# Proiect_TSC.net
KiCad netlist of a schematic drawn in EAGLE
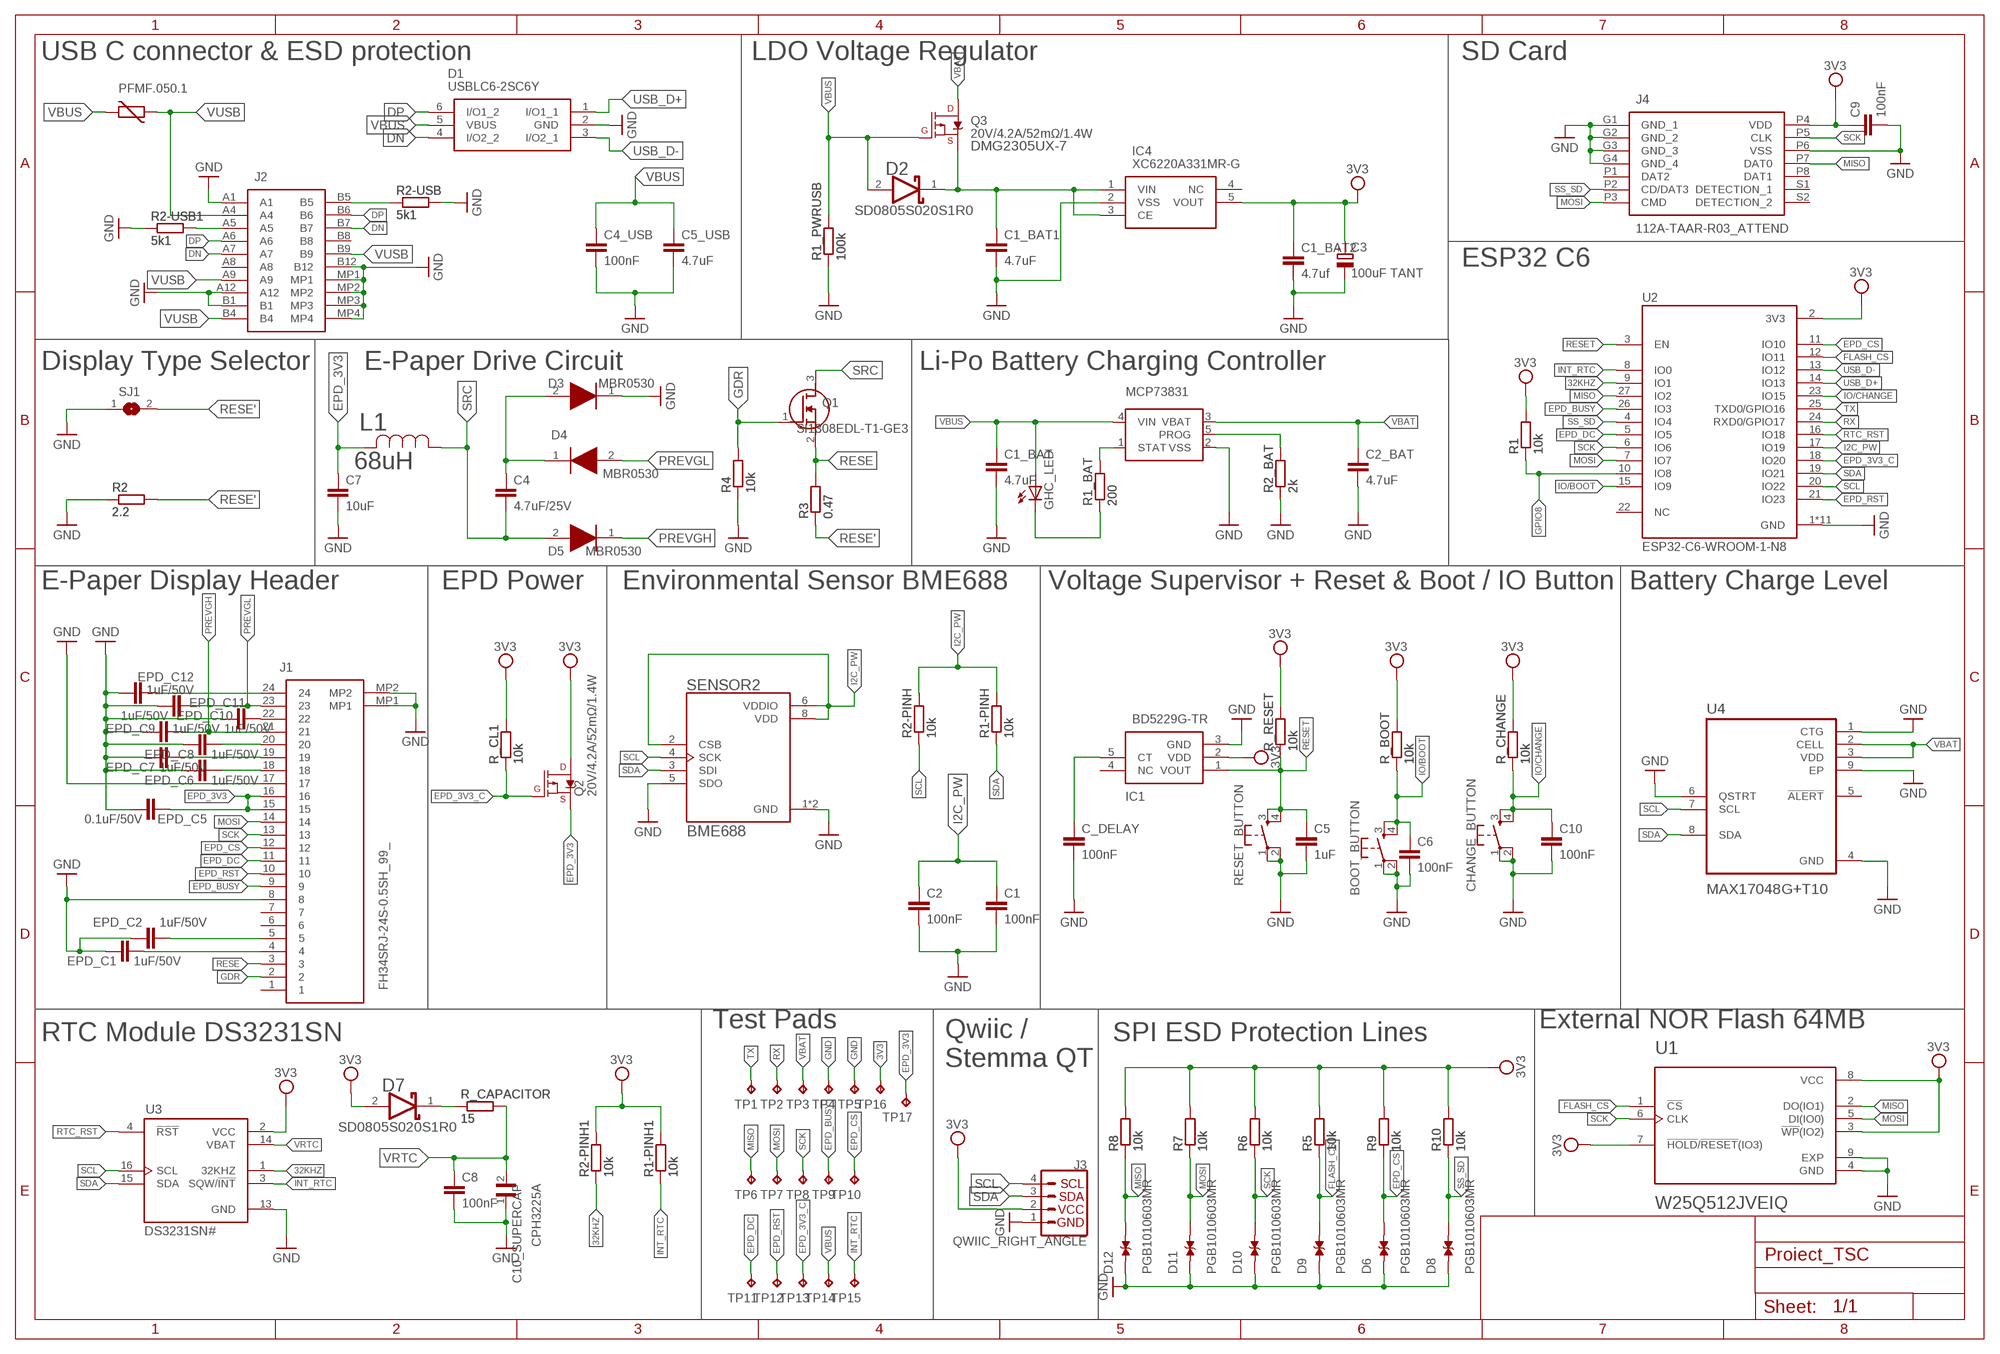
[diagram p0: schematic, sheet 1]

(export (version "E")
  (design (tool "Eeschema 10.0.6"))
  (components
    (comp (ref "BOOT_BUTTON")
      (value "BUTTON_CUSYOMV1")
      (footprint "eagle-import:MYBUTTON")
      (libsource (lib "eagle-import") (part "BUTTON_CUSYOMV1"))
    )
    (comp (ref "C1")
      (value "100nF")
      (footprint "eagle-import:ESP32_WROVER_EAGLE-LTSPICE_C0402")
      (libsource (lib "eagle-import") (part "ESP32_WROVER_EAGLE-LTSPICE_CC0402"))
    )
    (comp (ref "C1_BAT")
      (value "4.7uF")
      (footprint "eagle-import:EAGLE-LTSPICE_C0402")
      (libsource (lib "eagle-import") (part "EAGLE-LTSPICE_CC0402"))
    )
    (comp (ref "C1_BAT1")
      (value "4.7uF")
      (footprint "eagle-import:EAGLE-LTSPICE_C0402")
      (libsource (lib "eagle-import") (part "EAGLE-LTSPICE_CC0402"))
    )
    (comp (ref "C1_BAT2")
      (value "4.7uf")
      (footprint "eagle-import:EAGLE-LTSPICE_C0402")
      (libsource (lib "eagle-import") (part "EAGLE-LTSPICE_CC0402"))
    )
    (comp (ref "C2")
      (value "100nF")
      (footprint "eagle-import:ESP32_WROVER_EAGLE-LTSPICE_C0402")
      (libsource (lib "eagle-import") (part "ESP32_WROVER_EAGLE-LTSPICE_CC0402"))
    )
    (comp (ref "C2_BAT")
      (value "4.7uF")
      (footprint "eagle-import:EAGLE-LTSPICE_C0402")
      (libsource (lib "eagle-import") (part "EAGLE-LTSPICE_CC0402"))
    )
    (comp (ref "C3")
      (value "100uF TANT")
      (footprint "eagle-import:RCL_CT3528")
      (libsource (lib "eagle-import") (part "RCL_CPOL-EUCT3528"))
    )
    (comp (ref "C4")
      (value "4.7uF/25V")
      (footprint "eagle-import:ESP32_WROVER_EAGLE-LTSPICE_C0402")
      (libsource (lib "eagle-import") (part "ESP32_WROVER_EAGLE-LTSPICE_CC0402"))
    )
    (comp (ref "C4_USB")
      (value "100nF")
      (footprint "eagle-import:ESP32_WROVER_EAGLE-LTSPICE_C0402")
      (libsource (lib "eagle-import") (part "ESP32_WROVER_EAGLE-LTSPICE_CC0402"))
    )
    (comp (ref "C5")
      (value "1uF")
      (footprint "eagle-import:ESP32_WROVER_EAGLE-LTSPICE_C0402")
      (libsource (lib "eagle-import") (part "ESP32_WROVER_EAGLE-LTSPICE_CC0402"))
    )
    (comp (ref "C5_USB")
      (value "4.7uF")
      (footprint "eagle-import:ESP32_WROVER_EAGLE-LTSPICE_C0402")
      (libsource (lib "eagle-import") (part "ESP32_WROVER_EAGLE-LTSPICE_CC0402"))
    )
    (comp (ref "C6")
      (value "100nF")
      (footprint "eagle-import:ESP32_WROVER_EAGLE-LTSPICE_C0402")
      (libsource (lib "eagle-import") (part "ESP32_WROVER_EAGLE-LTSPICE_CC0402"))
    )
    (comp (ref "C7")
      (value "10uF")
      (footprint "eagle-import:ESP32_WROVER_EAGLE-LTSPICE_C0402")
      (libsource (lib "eagle-import") (part "ESP32_WROVER_EAGLE-LTSPICE_CC0402"))
    )
    (comp (ref "C8")
      (value "100nF")
      (footprint "eagle-import:ESP32_WROVER_EAGLE-LTSPICE_C0402")
      (libsource (lib "eagle-import") (part "ESP32_WROVER_EAGLE-LTSPICE_CC0402"))
    )
    (comp (ref "C9")
      (value "100nF")
      (footprint "eagle-import:ESP32_WROVER_EAGLE-LTSPICE_C0402")
      (libsource (lib "eagle-import") (part "ESP32_WROVER_EAGLE-LTSPICE_CC0402"))
    )
    (comp (ref "C10")
      (value "100nF")
      (footprint "eagle-import:ESP32_WROVER_EAGLE-LTSPICE_C0402")
      (libsource (lib "eagle-import") (part "ESP32_WROVER_EAGLE-LTSPICE_CC0402"))
    )
    (comp (ref "C10_SUPERCAP")
      (value "CPH3225A")
      (footprint "eagle-import:CAPCP3225X100N")
      (fields (field (name "MF") "Seiko Instruments"))
      (libsource (lib "eagle-import") (part "CPH3225A"))
    )
    (comp (ref "CHANGE_BUTTON")
      (value "BUTTON_CUSYOMV1")
      (footprint "eagle-import:MYBUTTON")
      (libsource (lib "eagle-import") (part "BUTTON_CUSYOMV1"))
    )
    (comp (ref "C_DELAY")
      (value "100nF")
      (footprint "eagle-import:ESP32_WROVER_EAGLE-LTSPICE_C0402")
      (libsource (lib "eagle-import") (part "ESP32_WROVER_EAGLE-LTSPICE_CC0402"))
    )
    (comp (ref "D1")
      (value "USBLC6-2SC6Y")
      (footprint "eagle-import:SOT95P280X145-6N")
      (fields (field (name "MF") "STMicroelectronics"))
      (libsource (lib "eagle-import") (part "USBLC6-2SC6Y"))
    )
    (comp (ref "D2")
      (value "SD0805S020S1R0")
      (footprint "eagle-import:ESP32_WROVER_AVX---SD0805S020S1R0_AVX_SD0805S020S1R0_0")
      (fields
        (field (name "DIGIKEY_PART_NUMBER") "478-7800-1-ND")
        (field (name "MF") "AVX")
        (field (name "MOUSER_PART_NUMBER") "581-SD0805S020S1R0")
      )
      (libsource (lib "eagle-import") (part "ESP32_WROVER_AVX---SD0805S020S1R0_AVX_SD0805S020S1R0_0_0AVX_SD0805S020S1R0_0_0"))
    )
    (comp (ref "D3")
      (value "MBR0530")
      (footprint "eagle-import:SOD3716X135N")
      (fields (field (name "MF") "ON Semiconductor"))
      (libsource (lib "eagle-import") (part "MBR0530"))
    )
    (comp (ref "D4")
      (value "MBR0530")
      (footprint "eagle-import:SOD3716X135N")
      (fields (field (name "MF") "ON Semiconductor"))
      (libsource (lib "eagle-import") (part "MBR0530"))
    )
    (comp (ref "D5")
      (value "MBR0530")
      (footprint "eagle-import:SOD3716X135N")
      (fields (field (name "MF") "ON Semiconductor"))
      (libsource (lib "eagle-import") (part "MBR0530"))
    )
    (comp (ref "D6")
      (value "PGB1010603MR")
      (footprint "eagle-import:DIOC1608X36N")
      (fields (field (name "MF") "Littelfuse Inc."))
      (libsource (lib "eagle-import") (part "PGB1010603MR"))
    )
    (comp (ref "D7")
      (value "ESP32_WROVER_AVX---SD0805S020S1R0_AVX_SD0805S020S1R0_0_0AVX_SD0805S020S1R0_0_0")
      (footprint "eagle-import:ESP32_WROVER_AVX---SD0805S020S1R0_AVX_SD0805S020S1R0_0")
      (fields
        (field (name "DIGIKEY_PART_NUMBER") "478-7800-1-ND")
        (field (name "MF") "AVX")
        (field (name "MOUSER_PART_NUMBER") "581-SD0805S020S1R0")
      )
      (libsource (lib "eagle-import") (part "ESP32_WROVER_AVX---SD0805S020S1R0_AVX_SD0805S020S1R0_0_0AVX_SD0805S020S1R0_0_0"))
    )
    (comp (ref "D8")
      (value "PGB1010603MR")
      (footprint "eagle-import:DIOC1608X36N")
      (fields (field (name "MF") "Littelfuse Inc."))
      (libsource (lib "eagle-import") (part "PGB1010603MR"))
    )
    (comp (ref "D9")
      (value "PGB1010603MR")
      (footprint "eagle-import:DIOC1608X36N")
      (fields (field (name "MF") "Littelfuse Inc."))
      (libsource (lib "eagle-import") (part "PGB1010603MR"))
    )
    (comp (ref "D10")
      (value "PGB1010603MR")
      (footprint "eagle-import:DIOC1608X36N")
      (fields (field (name "MF") "Littelfuse Inc."))
      (libsource (lib "eagle-import") (part "PGB1010603MR"))
    )
    (comp (ref "D11")
      (value "PGB1010603MR")
      (footprint "eagle-import:DIOC1608X36N")
      (fields (field (name "MF") "Littelfuse Inc."))
      (libsource (lib "eagle-import") (part "PGB1010603MR"))
    )
    (comp (ref "D12")
      (value "PGB1010603MR")
      (footprint "eagle-import:DIOC1608X36N")
      (fields (field (name "MF") "Littelfuse Inc."))
      (libsource (lib "eagle-import") (part "PGB1010603MR"))
    )
    (comp (ref "EPD_C1")
      (value "1uF/50V")
      (footprint "eagle-import:ESP32_WROVER_EAGLE-LTSPICE_C0402")
      (libsource (lib "eagle-import") (part "ESP32_WROVER_EAGLE-LTSPICE_CC0402"))
    )
    (comp (ref "EPD_C2")
      (value "1uF/50V")
      (footprint "eagle-import:ESP32_WROVER_EAGLE-LTSPICE_C0402")
      (libsource (lib "eagle-import") (part "ESP32_WROVER_EAGLE-LTSPICE_CC0402"))
    )
    (comp (ref "EPD_C5")
      (value "0.1uF/50V")
      (footprint "eagle-import:ESP32_WROVER_EAGLE-LTSPICE_C0402")
      (libsource (lib "eagle-import") (part "ESP32_WROVER_EAGLE-LTSPICE_CC0402"))
    )
    (comp (ref "EPD_C6")
      (value "1uF/50V")
      (footprint "eagle-import:ESP32_WROVER_EAGLE-LTSPICE_C0402")
      (libsource (lib "eagle-import") (part "ESP32_WROVER_EAGLE-LTSPICE_CC0402"))
    )
    (comp (ref "EPD_C7")
      (value "1uF/50V")
      (footprint "eagle-import:ESP32_WROVER_EAGLE-LTSPICE_C0402")
      (libsource (lib "eagle-import") (part "ESP32_WROVER_EAGLE-LTSPICE_CC0402"))
    )
    (comp (ref "EPD_C8")
      (value "1uF/50V")
      (footprint "eagle-import:ESP32_WROVER_EAGLE-LTSPICE_C0402")
      (libsource (lib "eagle-import") (part "ESP32_WROVER_EAGLE-LTSPICE_CC0402"))
    )
    (comp (ref "EPD_C9")
      (value "1uF/50V")
      (footprint "eagle-import:ESP32_WROVER_EAGLE-LTSPICE_C0402")
      (libsource (lib "eagle-import") (part "ESP32_WROVER_EAGLE-LTSPICE_CC0402"))
    )
    (comp (ref "EPD_C10")
      (value "1uF/50V")
      (footprint "eagle-import:ESP32_WROVER_EAGLE-LTSPICE_C0402")
      (libsource (lib "eagle-import") (part "ESP32_WROVER_EAGLE-LTSPICE_CC0402"))
    )
    (comp (ref "EPD_C11")
      (value "1uF/50V")
      (footprint "eagle-import:ESP32_WROVER_EAGLE-LTSPICE_C0402")
      (libsource (lib "eagle-import") (part "ESP32_WROVER_EAGLE-LTSPICE_CC0402"))
    )
    (comp (ref "EPD_C12")
      (value "1uF/50V")
      (footprint "eagle-import:ESP32_WROVER_EAGLE-LTSPICE_C0402")
      (libsource (lib "eagle-import") (part "ESP32_WROVER_EAGLE-LTSPICE_CC0402"))
    )
    (comp (ref "GHC_LED")
      (value "ADAFRUIT_LEDCHIP-LED0603")
      (footprint "eagle-import:ADAFRUIT_CHIP-LED0603")
      (libsource (lib "eagle-import") (part "ADAFRUIT_LEDCHIP-LED0603"))
    )
    (comp (ref "IC1")
      (value "BD5229G-TR")
      (footprint "eagle-import:SOT95P280X125-5N")
      (fields (field (name "MOUSER_PART_NUMBER") "755-BD5229G-TR"))
      (libsource (lib "eagle-import") (part "BD5229G-TR"))
    )
    (comp (ref "IC4")
      (value "XC6220A331MR-G")
      (footprint "eagle-import:SOT95P280X120-5N")
      (fields (field (name "MOUSER_PART_NUMBER") "865-XC6220A331MR-G"))
      (libsource (lib "eagle-import") (part "XC6220A331MR-G"))
    )
    (comp (ref "J1")
      (value "FH34SRJ-24S-0.5SH_99_")
      (footprint "eagle-import:FH34SRJ24S05SH99")
      (fields
        (field (name "MANUFACTURER_PART_NUMBER") "FH34SRJ-24S-0.5SH(99)")
        (field (name "MOUSER_PART_NUMBER") "798-FH34SRJ24S05SH99")
      )
      (libsource (lib "eagle-import") (part "FH34SRJ-24S-0.5SH_99_"))
    )
    (comp (ref "J2")
      (value "SAMACSYS_PARTS_USB4110-GF-A")
      (footprint "eagle-import:SAMACSYS_PARTS_USB4110GFA")
      (fields
        (field (name "MANUFACTURER_PART_NUMBER") "USB4110-GF-A")
        (field (name "MOUSER_PART_NUMBER") "640-USB4110-GF-A")
      )
      (libsource (lib "eagle-import") (part "SAMACSYS_PARTS_USB4110-GF-A"))
    )
    (comp (ref "J3")
      (value "QWIIC_RIGHT_ANGLE")
      (footprint "eagle-import:JST04_1MM_RA")
      (libsource (lib "eagle-import") (part "QWIIC_CONNECTORJS-1MM"))
    )
    (comp (ref "J4")
      (value "112A-TAAR-R03_ATTEND")
      (footprint "eagle-import:112ATAARR03ATTEND")
      (fields (field (name "MANUFACTURER_PART_NUMBER") "112A-TAAR-R03 ATTEND"))
      (libsource (lib "eagle-import") (part "112A-TAAR-R03_ATTEND"))
    )
    (comp (ref "L1")
      (value "68uH")
      (footprint "eagle-import:IND_4828-WE-TPC_WRE")
      (fields
        (field (name "MANUFACTURER_PART_NUMBER") "744043680")
        (field (name "COPYRIGHT") "Copyright (C) 2024 Ultra Librarian. All rights reserved.")
      )
      (libsource (lib "eagle-import") (part "744043680IND_4828-WE-TPC_WRE"))
    )
    (comp (ref "PFMF.050.1")
      (value "ESP32C6_VARISTORCN1812")
      (footprint "eagle-import:ESP32C6_VARISTOR_CT_CN1812")
      (libsource (lib "eagle-import") (part "ESP32C6_VARISTORCN1812"))
    )
    (comp (ref "Q1")
      (value "SI1308EDL-T1-GE3")
      (footprint "eagle-import:SOT65P210X110-3N")
      (fields (field (name "MF") "Vishay Siliconix"))
      (libsource (lib "eagle-import") (part "SI1308EDL-T1-GE3"))
    )
    (comp (ref "Q2")
      (value "20V/4.2A/52mΩ/1.4W")
      (footprint "eagle-import:ESP32_WROVER_SPARKFUN-DISCRETESEMI_SOT23-3")
      (libsource (lib "eagle-import") (part "ESP32_WROVER_SPARKFUN-DISCRETESEMI_MOSFET_PCH-DMG2305UX-7"))
    )
    (comp (ref "Q3")
      (value "20V/4.2A/52mΩ/1.4W")
      (footprint "eagle-import:ESP32_WROVER_SPARKFUN-DISCRETESEMI_SOT23-3")
      (libsource (lib "eagle-import") (part "ESP32_WROVER_SPARKFUN-DISCRETESEMI_MOSFET_PCH-DMG2305UX-7"))
    )
    (comp (ref "R1")
      (value "10k")
      (footprint "eagle-import:ESP32_WROVER_EAGLE-LTSPICE_R0402")
      (libsource (lib "eagle-import") (part "ESP32_WROVER_EAGLE-LTSPICE_RR0402"))
    )
    (comp (ref "R1-PINH")
      (value "10k")
      (footprint "eagle-import:ESP32_WROVER_EAGLE-LTSPICE_R0402")
      (libsource (lib "eagle-import") (part "ESP32_WROVER_EAGLE-LTSPICE_RR0402"))
    )
    (comp (ref "R1-PINH1")
      (value "10k")
      (footprint "eagle-import:ESP32_WROVER_EAGLE-LTSPICE_R0402")
      (libsource (lib "eagle-import") (part "ESP32_WROVER_EAGLE-LTSPICE_RR0402"))
    )
    (comp (ref "R1_BAT")
      (value "200")
      (footprint "eagle-import:ESP32_WROVER_EAGLE-LTSPICE_R0402")
      (libsource (lib "eagle-import") (part "ESP32_WROVER_EAGLE-LTSPICE_RR0402"))
    )
    (comp (ref "R1_PWRUSB")
      (value "100k")
      (footprint "eagle-import:ESP32_WROVER_EAGLE-LTSPICE_R0402")
      (libsource (lib "eagle-import") (part "ESP32_WROVER_EAGLE-LTSPICE_RR0402"))
    )
    (comp (ref "R2")
      (value "2.2")
      (footprint "eagle-import:ESP32_WROVER_EAGLE-LTSPICE_R0402")
      (libsource (lib "eagle-import") (part "ESP32_WROVER_EAGLE-LTSPICE_RR0402"))
    )
    (comp (ref "R2-PINH")
      (value "10k")
      (footprint "eagle-import:ESP32_WROVER_EAGLE-LTSPICE_R0402")
      (libsource (lib "eagle-import") (part "ESP32_WROVER_EAGLE-LTSPICE_RR0402"))
    )
    (comp (ref "R2-PINH1")
      (value "10k")
      (footprint "eagle-import:ESP32_WROVER_EAGLE-LTSPICE_R0402")
      (libsource (lib "eagle-import") (part "ESP32_WROVER_EAGLE-LTSPICE_RR0402"))
    )
    (comp (ref "R2-USB")
      (value "5k1")
      (footprint "eagle-import:ESP32_WROVER_EAGLE-LTSPICE_R0402")
      (libsource (lib "eagle-import") (part "ESP32_WROVER_EAGLE-LTSPICE_RR0402"))
    )
    (comp (ref "R2-USB1")
      (value "5k1")
      (footprint "eagle-import:ESP32_WROVER_EAGLE-LTSPICE_R0402")
      (libsource (lib "eagle-import") (part "ESP32_WROVER_EAGLE-LTSPICE_RR0402"))
    )
    (comp (ref "R2_BAT")
      (value "2k")
      (footprint "eagle-import:ESP32_WROVER_EAGLE-LTSPICE_R0402")
      (libsource (lib "eagle-import") (part "ESP32_WROVER_EAGLE-LTSPICE_RR0402"))
    )
    (comp (ref "R3")
      (value "0.47")
      (footprint "eagle-import:ESP32_WROVER_EAGLE-LTSPICE_R0402")
      (libsource (lib "eagle-import") (part "ESP32_WROVER_EAGLE-LTSPICE_RR0402"))
    )
    (comp (ref "R4")
      (value "10k")
      (footprint "eagle-import:ESP32_WROVER_EAGLE-LTSPICE_R0402")
      (libsource (lib "eagle-import") (part "ESP32_WROVER_EAGLE-LTSPICE_RR0402"))
    )
    (comp (ref "R5")
      (value "10k")
      (footprint "eagle-import:ESP32_WROVER_EAGLE-LTSPICE_R0402")
      (libsource (lib "eagle-import") (part "ESP32_WROVER_EAGLE-LTSPICE_RR0402"))
    )
    (comp (ref "R6")
      (value "10k")
      (footprint "eagle-import:ESP32_WROVER_EAGLE-LTSPICE_R0402")
      (libsource (lib "eagle-import") (part "ESP32_WROVER_EAGLE-LTSPICE_RR0402"))
    )
    (comp (ref "R7")
      (value "10k")
      (footprint "eagle-import:ESP32_WROVER_EAGLE-LTSPICE_R0402")
      (libsource (lib "eagle-import") (part "ESP32_WROVER_EAGLE-LTSPICE_RR0402"))
    )
    (comp (ref "R8")
      (value "10k")
      (footprint "eagle-import:ESP32_WROVER_EAGLE-LTSPICE_R0402")
      (libsource (lib "eagle-import") (part "ESP32_WROVER_EAGLE-LTSPICE_RR0402"))
    )
    (comp (ref "R9")
      (value "10k")
      (footprint "eagle-import:ESP32_WROVER_EAGLE-LTSPICE_R0402")
      (libsource (lib "eagle-import") (part "ESP32_WROVER_EAGLE-LTSPICE_RR0402"))
    )
    (comp (ref "R10")
      (value "10k")
      (footprint "eagle-import:ESP32_WROVER_EAGLE-LTSPICE_R0402")
      (libsource (lib "eagle-import") (part "ESP32_WROVER_EAGLE-LTSPICE_RR0402"))
    )
    (comp (ref "RESET_BUTTON")
      (value "BUTTON_CUSYOMV1")
      (footprint "eagle-import:MYBUTTON")
      (libsource (lib "eagle-import") (part "BUTTON_CUSYOMV1"))
    )
    (comp (ref "R_BOOT")
      (value "10k")
      (footprint "eagle-import:ESP32_WROVER_EAGLE-LTSPICE_R0402")
      (libsource (lib "eagle-import") (part "ESP32_WROVER_EAGLE-LTSPICE_RR0402"))
    )
    (comp (ref "R_CAPACITOR")
      (value "15")
      (footprint "eagle-import:ESP32_WROVER_EAGLE-LTSPICE_R0402")
      (libsource (lib "eagle-import") (part "ESP32_WROVER_EAGLE-LTSPICE_RR0402"))
    )
    (comp (ref "R_CHANGE")
      (value "10k")
      (footprint "eagle-import:ESP32_WROVER_EAGLE-LTSPICE_R0402")
      (libsource (lib "eagle-import") (part "ESP32_WROVER_EAGLE-LTSPICE_RR0402"))
    )
    (comp (ref "R_CL1")
      (value "10k")
      (footprint "eagle-import:ESP32_WROVER_EAGLE-LTSPICE_R0402")
      (libsource (lib "eagle-import") (part "ESP32_WROVER_EAGLE-LTSPICE_RR0402"))
    )
    (comp (ref "R_RESET")
      (value "10k")
      (footprint "eagle-import:ESP32_WROVER_EAGLE-LTSPICE_R0402")
      (libsource (lib "eagle-import") (part "ESP32_WROVER_EAGLE-LTSPICE_RR0402"))
    )
    (comp (ref "SENSOR2")
      (value "BME688")
      (footprint "eagle-import:ESP32_WROVER_BME680_PSON80P300X300X100-8N")
      (fields (field (name "MF") "Bosch Sensortec") (field (name "MP") "BME680"))
      (libsource (lib "eagle-import") (part "ESP32_WROVER_BME680_BME680"))
    )
    (comp (ref "SJ1") (value "SJ") (footprint "eagle-import:SJ") (libsource (lib "eagle-import") (part "SJ")))
    (comp (ref "TP1")
      (value "TPTP20R")
      (footprint "eagle-import:TP20R")
      (libsource (lib "eagle-import") (part "TPTP20R"))
    )
    (comp (ref "TP2")
      (value "TPTP20R")
      (footprint "eagle-import:TP20R")
      (libsource (lib "eagle-import") (part "TPTP20R"))
    )
    (comp (ref "TP3")
      (value "TPTP20R")
      (footprint "eagle-import:TP20R")
      (libsource (lib "eagle-import") (part "TPTP20R"))
    )
    (comp (ref "TP4")
      (value "TPTP20R")
      (footprint "eagle-import:TP20R")
      (libsource (lib "eagle-import") (part "TPTP20R"))
    )
    (comp (ref "TP5")
      (value "TPTP20R")
      (footprint "eagle-import:TP20R")
      (libsource (lib "eagle-import") (part "TPTP20R"))
    )
    (comp (ref "TP6")
      (value "TPTP20R")
      (footprint "eagle-import:TP20R")
      (libsource (lib "eagle-import") (part "TPTP20R"))
    )
    (comp (ref "TP7")
      (value "TPTP20R")
      (footprint "eagle-import:TP20R")
      (libsource (lib "eagle-import") (part "TPTP20R"))
    )
    (comp (ref "TP8")
      (value "TPTP20R")
      (footprint "eagle-import:TP20R")
      (libsource (lib "eagle-import") (part "TPTP20R"))
    )
    (comp (ref "TP9")
      (value "TPTP20R")
      (footprint "eagle-import:TP20R")
      (libsource (lib "eagle-import") (part "TPTP20R"))
    )
    (comp (ref "TP10")
      (value "TPTP20R")
      (footprint "eagle-import:TP20R")
      (libsource (lib "eagle-import") (part "TPTP20R"))
    )
    (comp (ref "TP11")
      (value "TPTP20R")
      (footprint "eagle-import:TP20R")
      (libsource (lib "eagle-import") (part "TPTP20R"))
    )
    (comp (ref "TP12")
      (value "TPTP20R")
      (footprint "eagle-import:TP20R")
      (libsource (lib "eagle-import") (part "TPTP20R"))
    )
    (comp (ref "TP13")
      (value "TPTP20R")
      (footprint "eagle-import:TP20R")
      (libsource (lib "eagle-import") (part "TPTP20R"))
    )
    (comp (ref "TP14")
      (value "TPTP20R")
      (footprint "eagle-import:TP20R")
      (libsource (lib "eagle-import") (part "TPTP20R"))
    )
    (comp (ref "TP15")
      (value "TPTP20R")
      (footprint "eagle-import:TP20R")
      (libsource (lib "eagle-import") (part "TPTP20R"))
    )
    (comp (ref "TP16")
      (value "TPTP20R")
      (footprint "eagle-import:TP20R")
      (libsource (lib "eagle-import") (part "TPTP20R"))
    )
    (comp (ref "TP17")
      (value "TPTP20R")
      (footprint "eagle-import:TP20R")
      (libsource (lib "eagle-import") (part "TPTP20R"))
    )
    (comp (ref "U")
      (value "MCP73831")
      (footprint "eagle-import:ESP32_WROVER_SPARKFUN-IC-POWER_SOT23-5")
      (libsource (lib "eagle-import") (part "ESP32_WROVER_SPARKFUN-IC-POWER_MCP73831"))
    )
    (comp (ref "U1")
      (value "W25Q512JVEIQ")
      (footprint "eagle-import:SON127P600X800X80-9N")
      (fields (field (name "MF") "Winbond Electronics"))
      (libsource (lib "eagle-import") (part "W25Q512JVEIQ"))
    )
    (comp (ref "U2")
      (value "ESP32-C6-WROOM-1-N8")
      (footprint "eagle-import:XCVR_ESP32-C6-WROOM-1-N8")
      (fields (field (name "MF") "Espressif Systems"))
      (libsource (lib "eagle-import") (part "ESP32-C6-WROOM-1-N8"))
    )
    (comp (ref "U3")
      (value "DS3231SN#")
      (footprint "eagle-import:SOIC127P1032X265-16N")
      (fields (field (name "MF") "Analog Devices"))
      (libsource (lib "eagle-import") (part "DS3231SN#"))
    )
    (comp (ref "U4")
      (value "MAX17048G+T10")
      (footprint "eagle-import:SON50P200X200X80-9N")
      (fields (field (name "MF") "Analog Devices"))
      (libsource (lib "eagle-import") (part "MAX17048G+T10"))
    )
  )
  (nets
    (net (code "1") (name "3V3") (class "Default")
      (node (ref "C1_BAT2") (pin "1") (pinfunction "1_1") (pintype "passive"))
      (node (ref "C3") (pin "+") (pinfunction "+_+") (pintype "passive"))
      (node (ref "C9") (pin "1") (pinfunction "1_1") (pintype "passive"))
      (node (ref "D7") (pin "2") (pinfunction "ANODE_2") (pintype "bidirectional"))
      (node (ref "IC1") (pin "2") (pinfunction "VDD_2") (pintype "bidirectional"))
      (node (ref "IC4") (pin "5") (pinfunction "VOUT_5") (pintype "bidirectional"))
      (node (ref "J3") (pin "2") (pinfunction "2_2") (pintype "power_in"))
      (node (ref "J4") (pin "P4") (pinfunction "VDD_P4") (pintype "bidirectional"))
      (node (ref "Q2") (pin "3") (pinfunction "D_3") (pintype "bidirectional"))
      (node (ref "R1") (pin "2") (pinfunction "2_2") (pintype "passive"))
      (node (ref "R1-PINH1") (pin "2") (pinfunction "2_2") (pintype "passive"))
      (node (ref "R10") (pin "2") (pinfunction "2_2") (pintype "passive"))
      (node (ref "R2-PINH1") (pin "2") (pinfunction "2_2") (pintype "passive"))
      (node (ref "R5") (pin "2") (pinfunction "2_2") (pintype "passive"))
      (node (ref "R6") (pin "2") (pinfunction "2_2") (pintype "passive"))
      (node (ref "R7") (pin "2") (pinfunction "2_2") (pintype "passive"))
      (node (ref "R8") (pin "2") (pinfunction "2_2") (pintype "passive"))
      (node (ref "R9") (pin "2") (pinfunction "2_2") (pintype "passive"))
      (node (ref "R_BOOT") (pin "2") (pinfunction "2_2") (pintype "passive"))
      (node (ref "R_CHANGE") (pin "2") (pinfunction "2_2") (pintype "passive"))
      (node (ref "R_CL1") (pin "2") (pinfunction "2_2") (pintype "passive"))
      (node (ref "R_RESET") (pin "2") (pinfunction "2_2") (pintype "passive"))
      (node (ref "TP16") (pin "TP") (pinfunction "TP_TP") (pintype "input"))
      (node (ref "U1") (pin "3") (pinfunction "~{WP}(IO2)_3") (pintype "bidirectional"))
      (node (ref "U1") (pin "7") (pinfunction "~{HOLD}/~{RESET}(IO3)_7") (pintype "bidirectional"))
      (node (ref "U1") (pin "8") (pinfunction "VCC_8") (pintype "power_in"))
      (node (ref "U2") (pin "2") (pinfunction "3V3_2") (pintype "power_in"))
      (node (ref "U3") (pin "2") (pinfunction "VCC_2") (pintype "power_in"))
    )
    (net (code "2") (name "32KHZ") (class "Default")
      (node (ref "R2-PINH1") (pin "1") (pinfunction "1_1") (pintype "passive"))
      (node (ref "U2") (pin "9") (pinfunction "IO1_9") (pintype "bidirectional"))
      (node (ref "U3") (pin "1") (pinfunction "32KHZ_1") (pintype "output"))
    )
    (net (code "3") (name "DN") (class "Default")
      (node (ref "D1") (pin "4") (pinfunction "I/O2_2_4") (pintype "bidirectional"))
      (node (ref "J2") (pin "A7") (pinfunction "A7_A7") (pintype "bidirectional"))
      (node (ref "J2") (pin "B7") (pinfunction "B7_B7") (pintype "bidirectional"))
    )
    (net (code "4") (name "DP") (class "Default")
      (node (ref "D1") (pin "6") (pinfunction "I/O1_2_6") (pintype "bidirectional"))
      (node (ref "J2") (pin "A6") (pinfunction "A6_A6") (pintype "bidirectional"))
      (node (ref "J2") (pin "B6") (pinfunction "B6_B6") (pintype "bidirectional"))
    )
    (net (code "5") (name "EPD_3V3") (class "Default")
      (node (ref "C7") (pin "1") (pinfunction "1_1") (pintype "passive"))
      (node (ref "EPD_C5") (pin "2") (pinfunction "2_2") (pintype "passive"))
      (node (ref "J1") (pin "15") (pinfunction "15_15") (pintype "bidirectional"))
      (node (ref "J1") (pin "16") (pinfunction "16_16") (pintype "bidirectional"))
      (node (ref "L1") (pin "2") (pinfunction "2_2") (pintype "passive"))
      (node (ref "Q2") (pin "2") (pinfunction "S_2") (pintype "bidirectional"))
      (node (ref "TP17") (pin "TP") (pinfunction "TP_TP") (pintype "input"))
    )
    (net (code "6") (name "EPD_3V3_C") (class "Default")
      (node (ref "Q2") (pin "1") (pinfunction "G_1") (pintype "bidirectional"))
      (node (ref "R_CL1") (pin "1") (pinfunction "1_1") (pintype "passive"))
      (node (ref "TP13") (pin "TP") (pinfunction "TP_TP") (pintype "input"))
      (node (ref "U2") (pin "18") (pinfunction "IO20_18") (pintype "bidirectional"))
    )
    (net (code "7") (name "EPD_BUSY") (class "Default")
      (node (ref "J1") (pin "9") (pinfunction "9_9") (pintype "bidirectional"))
      (node (ref "TP9") (pin "TP") (pinfunction "TP_TP") (pintype "input"))
      (node (ref "U2") (pin "26") (pinfunction "IO3_26") (pintype "bidirectional"))
    )
    (net (code "8") (name "EPD_CS") (class "Default")
      (node (ref "D6") (pin "2") (pinfunction "2_2") (pintype "passive"))
      (node (ref "J1") (pin "12") (pinfunction "12_12") (pintype "bidirectional"))
      (node (ref "R9") (pin "1") (pinfunction "1_1") (pintype "passive"))
      (node (ref "TP10") (pin "TP") (pinfunction "TP_TP") (pintype "input"))
      (node (ref "U2") (pin "11") (pinfunction "IO10_11") (pintype "bidirectional"))
    )
    (net (code "9") (name "EPD_DC") (class "Default")
      (node (ref "J1") (pin "11") (pinfunction "11_11") (pintype "bidirectional"))
      (node (ref "TP11") (pin "TP") (pinfunction "TP_TP") (pintype "input"))
      (node (ref "U2") (pin "5") (pinfunction "IO5_5") (pintype "bidirectional"))
    )
    (net (code "10") (name "EPD_RST") (class "Default")
      (node (ref "J1") (pin "10") (pinfunction "10_10") (pintype "bidirectional"))
      (node (ref "TP12") (pin "TP") (pinfunction "TP_TP") (pintype "input"))
      (node (ref "U2") (pin "21") (pinfunction "IO23_21") (pintype "bidirectional"))
    )
    (net (code "11") (name "FLASH_CS") (class "Default")
      (node (ref "D9") (pin "2") (pinfunction "2_2") (pintype "passive"))
      (node (ref "R5") (pin "1") (pinfunction "1_1") (pintype "passive"))
      (node (ref "U1") (pin "1") (pinfunction "~{CS}_1") (pintype "input"))
      (node (ref "U2") (pin "12") (pinfunction "IO11_12") (pintype "bidirectional"))
    )
    (net (code "12") (name "GDR") (class "Default")
      (node (ref "J1") (pin "2") (pinfunction "2_2") (pintype "bidirectional"))
      (node (ref "Q1") (pin "1") (pinfunction "G_1") (pintype "bidirectional"))
      (node (ref "R4") (pin "2") (pinfunction "2_2") (pintype "passive"))
    )
    (net (code "13") (name "GND") (class "Default")
      (node (ref "BOOT_BUTTON") (pin "1") (pinfunction "1_1") (pintype "passive"))
      (node (ref "BOOT_BUTTON") (pin "2") (pinfunction "2_2") (pintype "passive"))
      (node (ref "C1") (pin "2") (pinfunction "2_2") (pintype "passive"))
      (node (ref "C10") (pin "2") (pinfunction "2_2") (pintype "passive"))
      (node (ref "C10_SUPERCAP") (pin "1") (pinfunction "1_1") (pintype "passive"))
      (node (ref "C1_BAT") (pin "2") (pinfunction "2_2") (pintype "passive"))
      (node (ref "C1_BAT1") (pin "2") (pinfunction "2_2") (pintype "passive"))
      (node (ref "C1_BAT2") (pin "2") (pinfunction "2_2") (pintype "passive"))
      (node (ref "C2") (pin "2") (pinfunction "2_2") (pintype "passive"))
      (node (ref "C2_BAT") (pin "2") (pinfunction "2_2") (pintype "passive"))
      (node (ref "C3") (pin "-") (pinfunction "-_-") (pintype "passive"))
      (node (ref "C4_USB") (pin "2") (pinfunction "2_2") (pintype "passive"))
      (node (ref "C5") (pin "2") (pinfunction "2_2") (pintype "passive"))
      (node (ref "C5_USB") (pin "2") (pinfunction "2_2") (pintype "passive"))
      (node (ref "C6") (pin "2") (pinfunction "2_2") (pintype "passive"))
      (node (ref "C7") (pin "2") (pinfunction "2_2") (pintype "passive"))
      (node (ref "C8") (pin "2") (pinfunction "2_2") (pintype "passive"))
      (node (ref "C9") (pin "2") (pinfunction "2_2") (pintype "passive"))
      (node (ref "CHANGE_BUTTON") (pin "1") (pinfunction "1_1") (pintype "passive"))
      (node (ref "CHANGE_BUTTON") (pin "2") (pinfunction "2_2") (pintype "passive"))
      (node (ref "C_DELAY") (pin "2") (pinfunction "2_2") (pintype "passive"))
      (node (ref "D1") (pin "2") (pinfunction "GND_2") (pintype "bidirectional"))
      (node (ref "D10") (pin "1") (pinfunction "1_1") (pintype "passive"))
      (node (ref "D11") (pin "1") (pinfunction "1_1") (pintype "passive"))
      (node (ref "D12") (pin "1") (pinfunction "1_1") (pintype "passive"))
      (node (ref "D3") (pin "1") (pinfunction "K_1") (pintype "bidirectional"))
      (node (ref "D6") (pin "1") (pinfunction "1_1") (pintype "passive"))
      (node (ref "D8") (pin "1") (pinfunction "1_1") (pintype "passive"))
      (node (ref "D9") (pin "1") (pinfunction "1_1") (pintype "passive"))
      (node (ref "EPD_C1") (pin "1") (pinfunction "1_1") (pintype "passive"))
      (node (ref "EPD_C10") (pin "1") (pinfunction "1_1") (pintype "passive"))
      (node (ref "EPD_C11") (pin "1") (pinfunction "1_1") (pintype "passive"))
      (node (ref "EPD_C12") (pin "1") (pinfunction "1_1") (pintype "passive"))
      (node (ref "EPD_C2") (pin "1") (pinfunction "1_1") (pintype "passive"))
      (node (ref "EPD_C5") (pin "1") (pinfunction "1_1") (pintype "passive"))
      (node (ref "EPD_C6") (pin "1") (pinfunction "1_1") (pintype "passive"))
      (node (ref "EPD_C7") (pin "1") (pinfunction "1_1") (pintype "passive"))
      (node (ref "EPD_C8") (pin "1") (pinfunction "1_1") (pintype "passive"))
      (node (ref "EPD_C9") (pin "1") (pinfunction "1_1") (pintype "passive"))
      (node (ref "IC1") (pin "3") (pinfunction "GND_3") (pintype "bidirectional"))
      (node (ref "IC4") (pin "2") (pinfunction "VSS_2") (pintype "bidirectional"))
      (node (ref "J1") (pin "17") (pinfunction "17_17") (pintype "bidirectional"))
      (node (ref "J1") (pin "8") (pinfunction "8_8") (pintype "bidirectional"))
      (node (ref "J1") (pin "MP1") (pinfunction "MP1_MP1") (pintype "bidirectional"))
      (node (ref "J1") (pin "MP2") (pinfunction "MP2_MP2") (pintype "bidirectional"))
      (node (ref "J2") (pin "A1") (pinfunction "A1_A1") (pintype "bidirectional"))
      (node (ref "J2") (pin "A12") (pinfunction "A12_A12") (pintype "bidirectional"))
      (node (ref "J2") (pin "B1") (pinfunction "B1_B1") (pintype "bidirectional"))
      (node (ref "J2") (pin "B12") (pinfunction "B12_B12") (pintype "bidirectional"))
      (node (ref "J2") (pin "MP1") (pinfunction "MP1_MP1") (pintype "bidirectional"))
      (node (ref "J2") (pin "MP2") (pinfunction "MP2_MP2") (pintype "bidirectional"))
      (node (ref "J2") (pin "MP3") (pinfunction "MP3_MP3") (pintype "bidirectional"))
      (node (ref "J2") (pin "MP4") (pinfunction "MP4_MP4") (pintype "bidirectional"))
      (node (ref "J3") (pin "1") (pinfunction "1_1") (pintype "power_in"))
      (node (ref "J4") (pin "G1") (pinfunction "GND_1_G1") (pintype "bidirectional"))
      (node (ref "J4") (pin "G2") (pinfunction "GND_2_G2") (pintype "bidirectional"))
      (node (ref "J4") (pin "G3") (pinfunction "GND_3_G3") (pintype "bidirectional"))
      (node (ref "J4") (pin "G4") (pinfunction "GND_4_G4") (pintype "bidirectional"))
      (node (ref "J4") (pin "P6") (pinfunction "VSS_P6") (pintype "bidirectional"))
      (node (ref "R1_PWRUSB") (pin "1") (pinfunction "1_1") (pintype "passive"))
      (node (ref "R2") (pin "1") (pinfunction "1_1") (pintype "passive"))
      (node (ref "R2-USB") (pin "2") (pinfunction "2_2") (pintype "passive"))
      (node (ref "R2-USB1") (pin "1") (pinfunction "1_1") (pintype "passive"))
      (node (ref "R2_BAT") (pin "1") (pinfunction "1_1") (pintype "passive"))
      (node (ref "R4") (pin "1") (pinfunction "1_1") (pintype "passive"))
      (node (ref "RESET_BUTTON") (pin "1") (pinfunction "1_1") (pintype "passive"))
      (node (ref "RESET_BUTTON") (pin "2") (pinfunction "2_2") (pintype "passive"))
      (node (ref "SENSOR2") (pin "1") (pinfunction "GND_1") (pintype "power_in"))
      (node (ref "SENSOR2") (pin "5") (pinfunction "SDO_5") (pintype "bidirectional"))
      (node (ref "SENSOR2") (pin "7") (pinfunction "GND_7") (pintype "power_in"))
      (node (ref "SJ1") (pin "1") (pinfunction "1_1") (pintype "passive"))
      (node (ref "TP4") (pin "TP") (pinfunction "TP_TP") (pintype "input"))
      (node (ref "TP5") (pin "TP") (pinfunction "TP_TP") (pintype "input"))
      (node (ref "U") (pin "2") (pinfunction "VSS_2") (pintype "power_in"))
      (node (ref "U1") (pin "4") (pinfunction "GND_4") (pintype "power_in"))
      (node (ref "U1") (pin "9") (pinfunction "EXP_9") (pintype "passive"))
      (node (ref "U2") (pin "1") (pinfunction "GND_1") (pintype "power_in"))
      (node (ref "U2") (pin "28") (pinfunction "GND_28") (pintype "power_in"))
      (node (ref "U2") (pin "29_1") (pinfunction "GND_29_1") (pintype "power_in"))
      (node (ref "U2") (pin "29_2") (pinfunction "GND_29_2") (pintype "power_in"))
      (node (ref "U2") (pin "29_3") (pinfunction "GND_29_3") (pintype "power_in"))
      (node (ref "U2") (pin "29_4") (pinfunction "GND_29_4") (pintype "power_in"))
      (node (ref "U2") (pin "29_5") (pinfunction "GND_29_5") (pintype "power_in"))
      (node (ref "U2") (pin "29_6") (pinfunction "GND_29_6") (pintype "power_in"))
      (node (ref "U2") (pin "29_7") (pinfunction "GND_29_7") (pintype "power_in"))
      (node (ref "U2") (pin "29_8") (pinfunction "GND_29_8") (pintype "power_in"))
      (node (ref "U2") (pin "29_9") (pinfunction "GND_29_9") (pintype "power_in"))
      (node (ref "U3") (pin "13") (pinfunction "GND_13") (pintype "power_in"))
      (node (ref "U4") (pin "1") (pinfunction "CTG_1") (pintype "power_in"))
      (node (ref "U4") (pin "4") (pinfunction "GND_4") (pintype "power_in"))
      (node (ref "U4") (pin "6") (pinfunction "QSTRT_6") (pintype "input"))
      (node (ref "U4") (pin "9") (pinfunction "EP_9") (pintype "power_in"))
    )
    (net (code "14") (name "GPIO8") (class "Default")
      (node (ref "R1") (pin "1") (pinfunction "1_1") (pintype "passive"))
      (node (ref "U2") (pin "10") (pinfunction "IO8_10") (pintype "bidirectional"))
    )
    (net (code "15") (name "I2C_PW") (class "Default")
      (node (ref "C1") (pin "1") (pinfunction "1_1") (pintype "passive"))
      (node (ref "C2") (pin "1") (pinfunction "1_1") (pintype "passive"))
      (node (ref "R1-PINH") (pin "2") (pinfunction "2_2") (pintype "passive"))
      (node (ref "R2-PINH") (pin "2") (pinfunction "2_2") (pintype "passive"))
      (node (ref "SENSOR2") (pin "2") (pinfunction "CSB_2") (pintype "input"))
      (node (ref "SENSOR2") (pin "6") (pinfunction "VDDIO_6") (pintype "power_in"))
      (node (ref "SENSOR2") (pin "8") (pinfunction "VDD_8") (pintype "power_in"))
      (node (ref "U2") (pin "17") (pinfunction "IO19_17") (pintype "bidirectional"))
    )
    (net (code "16") (name "INT_RTC") (class "Default")
      (node (ref "R1-PINH1") (pin "1") (pinfunction "1_1") (pintype "passive"))
      (node (ref "TP15") (pin "TP") (pinfunction "TP_TP") (pintype "input"))
      (node (ref "U2") (pin "8") (pinfunction "IO0_8") (pintype "bidirectional"))
      (node (ref "U3") (pin "3") (pinfunction "SQW/~{INT}_3") (pintype "output"))
    )
    (net (code "17") (name "IO{slash}BOOT") (class "Default")
      (node (ref "BOOT_BUTTON") (pin "3") (pinfunction "3_3") (pintype "passive"))
      (node (ref "BOOT_BUTTON") (pin "4") (pinfunction "4_4") (pintype "passive"))
      (node (ref "C6") (pin "1") (pinfunction "1_1") (pintype "passive"))
      (node (ref "R_BOOT") (pin "1") (pinfunction "1_1") (pintype "passive"))
      (node (ref "U2") (pin "15") (pinfunction "IO9_15") (pintype "bidirectional"))
    )
    (net (code "18") (name "IO{slash}CHANGE") (class "Default")
      (node (ref "C10") (pin "1") (pinfunction "1_1") (pintype "passive"))
      (node (ref "CHANGE_BUTTON") (pin "3") (pinfunction "3_3") (pintype "passive"))
      (node (ref "CHANGE_BUTTON") (pin "4") (pinfunction "4_4") (pintype "passive"))
      (node (ref "R_CHANGE") (pin "1") (pinfunction "1_1") (pintype "passive"))
      (node (ref "U2") (pin "23") (pinfunction "IO15_23") (pintype "bidirectional"))
    )
    (net (code "19") (name "MISO") (class "Default")
      (node (ref "D12") (pin "2") (pinfunction "2_2") (pintype "passive"))
      (node (ref "J4") (pin "P7") (pinfunction "DAT0_P7") (pintype "bidirectional"))
      (node (ref "R8") (pin "1") (pinfunction "1_1") (pintype "passive"))
      (node (ref "TP6") (pin "TP") (pinfunction "TP_TP") (pintype "input"))
      (node (ref "U1") (pin "2") (pinfunction "DO(IO1)_2") (pintype "bidirectional"))
      (node (ref "U2") (pin "27") (pinfunction "IO2_27") (pintype "bidirectional"))
    )
    (net (code "20") (name "MOSI") (class "Default")
      (node (ref "D11") (pin "2") (pinfunction "2_2") (pintype "passive"))
      (node (ref "J1") (pin "14") (pinfunction "14_14") (pintype "bidirectional"))
      (node (ref "J4") (pin "P3") (pinfunction "CMD_P3") (pintype "bidirectional"))
      (node (ref "R7") (pin "1") (pinfunction "1_1") (pintype "passive"))
      (node (ref "TP7") (pin "TP") (pinfunction "TP_TP") (pintype "input"))
      (node (ref "U1") (pin "5") (pinfunction "DI(IO0)_5") (pintype "bidirectional"))
      (node (ref "U2") (pin "7") (pinfunction "IO7_7") (pintype "bidirectional"))
    )
    (net (code "21") (name "Net-(D2-CATHODE)") (class "Default")
      (node (ref "C1_BAT1") (pin "1") (pinfunction "1_1") (pintype "passive"))
      (node (ref "D2") (pin "1") (pinfunction "CATHODE_1") (pintype "bidirectional"))
      (node (ref "IC4") (pin "1") (pinfunction "VIN_1") (pintype "bidirectional"))
      (node (ref "IC4") (pin "3") (pinfunction "CE_3") (pintype "bidirectional"))
      (node (ref "Q3") (pin "2") (pinfunction "S_2") (pintype "bidirectional"))
    )
    (net (code "22") (name "Net-(D3-A)") (class "Default")
      (node (ref "C4") (pin "1") (pinfunction "1_1") (pintype "passive"))
      (node (ref "D3") (pin "2") (pinfunction "A_2") (pintype "bidirectional"))
      (node (ref "D4") (pin "1") (pinfunction "K_1") (pintype "bidirectional"))
    )
    (net (code "23") (name "Net-(D7-CATHODE)") (class "Default")
      (node (ref "D7") (pin "1") (pinfunction "CATHODE_1") (pintype "bidirectional"))
      (node (ref "R_CAPACITOR") (pin "1") (pinfunction "1_1") (pintype "passive"))
    )
    (net (code "24") (name "Net-(EPD_C1-Pad2)") (class "Default")
      (node (ref "EPD_C1") (pin "2") (pinfunction "2_2") (pintype "passive"))
      (node (ref "J1") (pin "4") (pinfunction "4_4") (pintype "bidirectional"))
    )
    (net (code "25") (name "Net-(EPD_C2-Pad2)") (class "Default")
      (node (ref "EPD_C2") (pin "2") (pinfunction "2_2") (pintype "passive"))
      (node (ref "J1") (pin "5") (pinfunction "5_5") (pintype "bidirectional"))
    )
    (net (code "26") (name "Net-(EPD_C6-Pad2)") (class "Default")
      (node (ref "EPD_C6") (pin "2") (pinfunction "2_2") (pintype "passive"))
      (node (ref "J1") (pin "18") (pinfunction "18_18") (pintype "bidirectional"))
    )
    (net (code "27") (name "Net-(EPD_C7-Pad2)") (class "Default")
      (node (ref "EPD_C7") (pin "2") (pinfunction "2_2") (pintype "passive"))
      (node (ref "J1") (pin "19") (pinfunction "19_19") (pintype "bidirectional"))
    )
    (net (code "28") (name "Net-(EPD_C8-Pad2)") (class "Default")
      (node (ref "EPD_C8") (pin "2") (pinfunction "2_2") (pintype "passive"))
      (node (ref "J1") (pin "20") (pinfunction "20_20") (pintype "bidirectional"))
    )
    (net (code "29") (name "Net-(EPD_C10-Pad2)") (class "Default")
      (node (ref "EPD_C10") (pin "2") (pinfunction "2_2") (pintype "passive"))
      (node (ref "J1") (pin "22") (pinfunction "22_22") (pintype "bidirectional"))
    )
    (net (code "30") (name "Net-(EPD_C12-Pad2)") (class "Default")
      (node (ref "EPD_C12") (pin "2") (pinfunction "2_2") (pintype "passive"))
      (node (ref "J1") (pin "24") (pinfunction "24_24") (pintype "bidirectional"))
    )
    (net (code "31") (name "Net-(GHC_LED-PadC)") (class "Default")
      (node (ref "GHC_LED") (pin "C") (pinfunction "C_C") (pintype "passive"))
      (node (ref "R1_BAT") (pin "1") (pinfunction "1_1") (pintype "passive"))
    )
    (net (code "32") (name "Net-(IC1-CT)") (class "Default")
      (node (ref "C_DELAY") (pin "1") (pinfunction "1_1") (pintype "passive"))
      (node (ref "IC1") (pin "5") (pinfunction "CT_5") (pintype "bidirectional"))
    )
    (net (code "33") (name "Net-(J2-PadA5)") (class "Default")
      (node (ref "J2") (pin "A5") (pinfunction "A5_A5") (pintype "bidirectional"))
      (node (ref "R2-USB1") (pin "2") (pinfunction "2_2") (pintype "passive"))
    )
    (net (code "34") (name "Net-(J2-PadB5)") (class "Default")
      (node (ref "J2") (pin "B5") (pinfunction "B5_B5") (pintype "bidirectional"))
      (node (ref "R2-USB") (pin "1") (pinfunction "1_1") (pintype "passive"))
    )
    (net (code "35") (name "Net-(U-PROG)") (class "Default")
      (node (ref "R2_BAT") (pin "2") (pinfunction "2_2") (pintype "passive"))
      (node (ref "U") (pin "5") (pinfunction "PROG_5") (pintype "input"))
    )
    (net (code "36") (name "Net-(U-STAT)") (class "Default")
      (node (ref "R1_BAT") (pin "2") (pinfunction "2_2") (pintype "passive"))
      (node (ref "U") (pin "1") (pinfunction "STAT_1") (pintype "output"))
    )
    (net (code "37") (name "PREVGH") (class "Default")
      (node (ref "D5") (pin "1") (pinfunction "K_1") (pintype "bidirectional"))
      (node (ref "EPD_C9") (pin "2") (pinfunction "2_2") (pintype "passive"))
      (node (ref "J1") (pin "21") (pinfunction "21_21") (pintype "bidirectional"))
    )
    (net (code "38") (name "PREVGL") (class "Default")
      (node (ref "D4") (pin "2") (pinfunction "A_2") (pintype "bidirectional"))
      (node (ref "EPD_C11") (pin "2") (pinfunction "2_2") (pintype "passive"))
      (node (ref "J1") (pin "23") (pinfunction "23_23") (pintype "bidirectional"))
    )
    (net (code "39") (name "RESE") (class "Default")
      (node (ref "J1") (pin "3") (pinfunction "3_3") (pintype "bidirectional"))
      (node (ref "Q1") (pin "2") (pinfunction "S_2") (pintype "bidirectional"))
      (node (ref "R3") (pin "2") (pinfunction "2_2") (pintype "passive"))
    )
    (net (code "40") (name "RESE'") (class "Default")
      (node (ref "R2") (pin "2") (pinfunction "2_2") (pintype "passive"))
      (node (ref "R3") (pin "1") (pinfunction "1_1") (pintype "passive"))
      (node (ref "SJ1") (pin "2") (pinfunction "2_2") (pintype "passive"))
    )
    (net (code "41") (name "RESET") (class "Default")
      (node (ref "C5") (pin "1") (pinfunction "1_1") (pintype "passive"))
      (node (ref "IC1") (pin "1") (pinfunction "VOUT_1") (pintype "bidirectional"))
      (node (ref "RESET_BUTTON") (pin "3") (pinfunction "3_3") (pintype "passive"))
      (node (ref "RESET_BUTTON") (pin "4") (pinfunction "4_4") (pintype "passive"))
      (node (ref "R_RESET") (pin "1") (pinfunction "1_1") (pintype "passive"))
      (node (ref "U2") (pin "3") (pinfunction "EN_3") (pintype "input"))
    )
    (net (code "42") (name "RTC_RST") (class "Default")
      (node (ref "U2") (pin "16") (pinfunction "IO18_16") (pintype "bidirectional"))
      (node (ref "U3") (pin "4") (pinfunction "~{RST}_4") (pintype "input"))
    )
    (net (code "43") (name "RX") (class "Default")
      (node (ref "TP2") (pin "TP") (pinfunction "TP_TP") (pintype "input"))
      (node (ref "U2") (pin "24") (pinfunction "RXD0/GPIO17_24") (pintype "bidirectional"))
    )
    (net (code "44") (name "SCK") (class "Default")
      (node (ref "D10") (pin "2") (pinfunction "2_2") (pintype "passive"))
      (node (ref "J1") (pin "13") (pinfunction "13_13") (pintype "bidirectional"))
      (node (ref "J4") (pin "P5") (pinfunction "CLK_P5") (pintype "bidirectional"))
      (node (ref "R6") (pin "1") (pinfunction "1_1") (pintype "passive"))
      (node (ref "TP8") (pin "TP") (pinfunction "TP_TP") (pintype "input"))
      (node (ref "U1") (pin "6") (pinfunction "CLK_6") (pintype "input"))
      (node (ref "U2") (pin "6") (pinfunction "IO6_6") (pintype "bidirectional"))
    )
    (net (code "45") (name "SCL") (class "Default")
      (node (ref "J3") (pin "4") (pinfunction "4_4") (pintype "passive"))
      (node (ref "R2-PINH") (pin "1") (pinfunction "1_1") (pintype "passive"))
      (node (ref "SENSOR2") (pin "4") (pinfunction "SCK_4") (pintype "input"))
      (node (ref "U2") (pin "20") (pinfunction "IO22_20") (pintype "bidirectional"))
      (node (ref "U3") (pin "16") (pinfunction "SCL_16") (pintype "input"))
      (node (ref "U4") (pin "7") (pinfunction "SCL_7") (pintype "input"))
    )
    (net (code "46") (name "SDA") (class "Default")
      (node (ref "J3") (pin "3") (pinfunction "3_3") (pintype "passive"))
      (node (ref "R1-PINH") (pin "1") (pinfunction "1_1") (pintype "passive"))
      (node (ref "SENSOR2") (pin "3") (pinfunction "SDI_3") (pintype "bidirectional"))
      (node (ref "U2") (pin "19") (pinfunction "IO21_19") (pintype "bidirectional"))
      (node (ref "U3") (pin "15") (pinfunction "SDA_15") (pintype "bidirectional"))
      (node (ref "U4") (pin "8") (pinfunction "SDA_8") (pintype "bidirectional"))
    )
    (net (code "47") (name "SRC") (class "Default")
      (node (ref "C4") (pin "2") (pinfunction "2_2") (pintype "passive"))
      (node (ref "D5") (pin "2") (pinfunction "A_2") (pintype "bidirectional"))
      (node (ref "L1") (pin "1") (pinfunction "1_1") (pintype "passive"))
      (node (ref "Q1") (pin "3") (pinfunction "D_3") (pintype "bidirectional"))
    )
    (net (code "48") (name "SS_SD") (class "Default")
      (node (ref "D8") (pin "2") (pinfunction "2_2") (pintype "passive"))
      (node (ref "J4") (pin "P2") (pinfunction "CD/DAT3_P2") (pintype "bidirectional"))
      (node (ref "R10") (pin "1") (pinfunction "1_1") (pintype "passive"))
      (node (ref "U2") (pin "4") (pinfunction "IO4_4") (pintype "bidirectional"))
    )
    (net (code "49") (name "TX") (class "Default")
      (node (ref "TP1") (pin "TP") (pinfunction "TP_TP") (pintype "input"))
      (node (ref "U2") (pin "25") (pinfunction "TXD0/GPIO16_25") (pintype "bidirectional"))
    )
    (net (code "50") (name "USB_D+") (class "Default")
      (node (ref "D1") (pin "1") (pinfunction "I/O1_1_1") (pintype "bidirectional"))
      (node (ref "U2") (pin "14") (pinfunction "IO13_14") (pintype "bidirectional"))
    )
    (net (code "51") (name "USB_D-") (class "Default")
      (node (ref "D1") (pin "3") (pinfunction "I/O2_1_3") (pintype "bidirectional"))
      (node (ref "U2") (pin "13") (pinfunction "IO12_13") (pintype "bidirectional"))
    )
    (net (code "52") (name "VBAT") (class "Default")
      (node (ref "C2_BAT") (pin "1") (pinfunction "1_1") (pintype "passive"))
      (node (ref "Q3") (pin "3") (pinfunction "D_3") (pintype "bidirectional"))
      (node (ref "TP3") (pin "TP") (pinfunction "TP_TP") (pintype "input"))
      (node (ref "U") (pin "3") (pinfunction "VBAT_3") (pintype "power_in"))
      (node (ref "U4") (pin "2") (pinfunction "CELL_2") (pintype "power_in"))
      (node (ref "U4") (pin "3") (pinfunction "VDD_3") (pintype "power_in"))
    )
    (net (code "53") (name "VBUS") (class "Default")
      (node (ref "C1_BAT") (pin "1") (pinfunction "1_1") (pintype "passive"))
      (node (ref "C4_USB") (pin "1") (pinfunction "1_1") (pintype "passive"))
      (node (ref "C5_USB") (pin "1") (pinfunction "1_1") (pintype "passive"))
      (node (ref "D1") (pin "5") (pinfunction "VBUS_5") (pintype "bidirectional"))
      (node (ref "D2") (pin "2") (pinfunction "ANODE_2") (pintype "bidirectional"))
      (node (ref "GHC_LED") (pin "A") (pinfunction "A_A") (pintype "passive"))
      (node (ref "PFMF.050.1") (pin "2") (pinfunction "2_2") (pintype "passive"))
      (node (ref "Q3") (pin "1") (pinfunction "G_1") (pintype "bidirectional"))
      (node (ref "R1_PWRUSB") (pin "2") (pinfunction "2_2") (pintype "passive"))
      (node (ref "TP14") (pin "TP") (pinfunction "TP_TP") (pintype "input"))
      (node (ref "U") (pin "4") (pinfunction "VIN_4") (pintype "power_in"))
    )
    (net (code "54") (name "VRTC") (class "Default")
      (node (ref "C10_SUPERCAP") (pin "2") (pinfunction "2_2") (pintype "passive"))
      (node (ref "C8") (pin "1") (pinfunction "1_1") (pintype "passive"))
      (node (ref "R_CAPACITOR") (pin "2") (pinfunction "2_2") (pintype "passive"))
      (node (ref "U3") (pin "14") (pinfunction "VBAT_14") (pintype "power_in"))
    )
    (net (code "55") (name "VUSB") (class "Default")
      (node (ref "J2") (pin "A4") (pinfunction "A4_A4") (pintype "bidirectional"))
      (node (ref "J2") (pin "A9") (pinfunction "A9_A9") (pintype "bidirectional"))
      (node (ref "J2") (pin "B4") (pinfunction "B4_B4") (pintype "bidirectional"))
      (node (ref "J2") (pin "B9") (pinfunction "B9_B9") (pintype "bidirectional"))
      (node (ref "PFMF.050.1") (pin "1") (pinfunction "1_1") (pintype "passive"))
    )
    (net (code "56") (name "unconnected-(IC1-NC-Pad4)") (class "Default")
      (node (ref "IC1") (pin "4") (pinfunction "NC_4") (pintype "no_connect"))
    )
    (net (code "57") (name "unconnected-(IC4-NC-Pad4)") (class "Default")
      (node (ref "IC4") (pin "4") (pinfunction "NC_4") (pintype "no_connect"))
    )
    (net (code "58") (name "unconnected-(J1-Pad1)") (class "Default")
      (node (ref "J1") (pin "1") (pinfunction "1_1") (pintype "bidirectional"))
    )
    (net (code "59") (name "unconnected-(J1-Pad6)") (class "Default")
      (node (ref "J1") (pin "6") (pinfunction "6_6") (pintype "bidirectional"))
    )
    (net (code "60") (name "unconnected-(J1-Pad7)") (class "Default")
      (node (ref "J1") (pin "7") (pinfunction "7_7") (pintype "bidirectional"))
    )
    (net (code "61") (name "unconnected-(J2-PadA8)") (class "Default")
      (node (ref "J2") (pin "A8") (pinfunction "A8_A8") (pintype "bidirectional"))
    )
    (net (code "62") (name "unconnected-(J2-PadB8)") (class "Default")
      (node (ref "J2") (pin "B8") (pinfunction "B8_B8") (pintype "bidirectional"))
    )
    (net (code "63") (name "unconnected-(J4-DAT1-PadP8)") (class "Default")
      (node (ref "J4") (pin "P8") (pinfunction "DAT1_P8") (pintype "bidirectional"))
    )
    (net (code "64") (name "unconnected-(J4-DAT2-PadP1)") (class "Default")
      (node (ref "J4") (pin "P1") (pinfunction "DAT2_P1") (pintype "bidirectional"))
    )
    (net (code "65") (name "unconnected-(J4-DETECTION_1-PadS1)") (class "Default")
      (node (ref "J4") (pin "S1") (pinfunction "DETECTION_1_S1") (pintype "bidirectional"))
    )
    (net (code "66") (name "unconnected-(J4-DETECTION_2-PadS2)") (class "Default")
      (node (ref "J4") (pin "S2") (pinfunction "DETECTION_2_S2") (pintype "bidirectional"))
    )
    (net (code "67") (name "unconnected-(U2-NC-Pad22)") (class "Default")
      (node (ref "U2") (pin "22") (pinfunction "NC_22") (pintype "no_connect"))
    )
    (net (code "68") (name "unconnected-(U4-~{ALERT}-Pad5)") (class "Default")
      (node (ref "U4") (pin "5") (pinfunction "~{ALERT}_5") (pintype "output"))
    )
  )
)
